# Output.net
KiCad netlist of a schematic drawn in Altium Designer
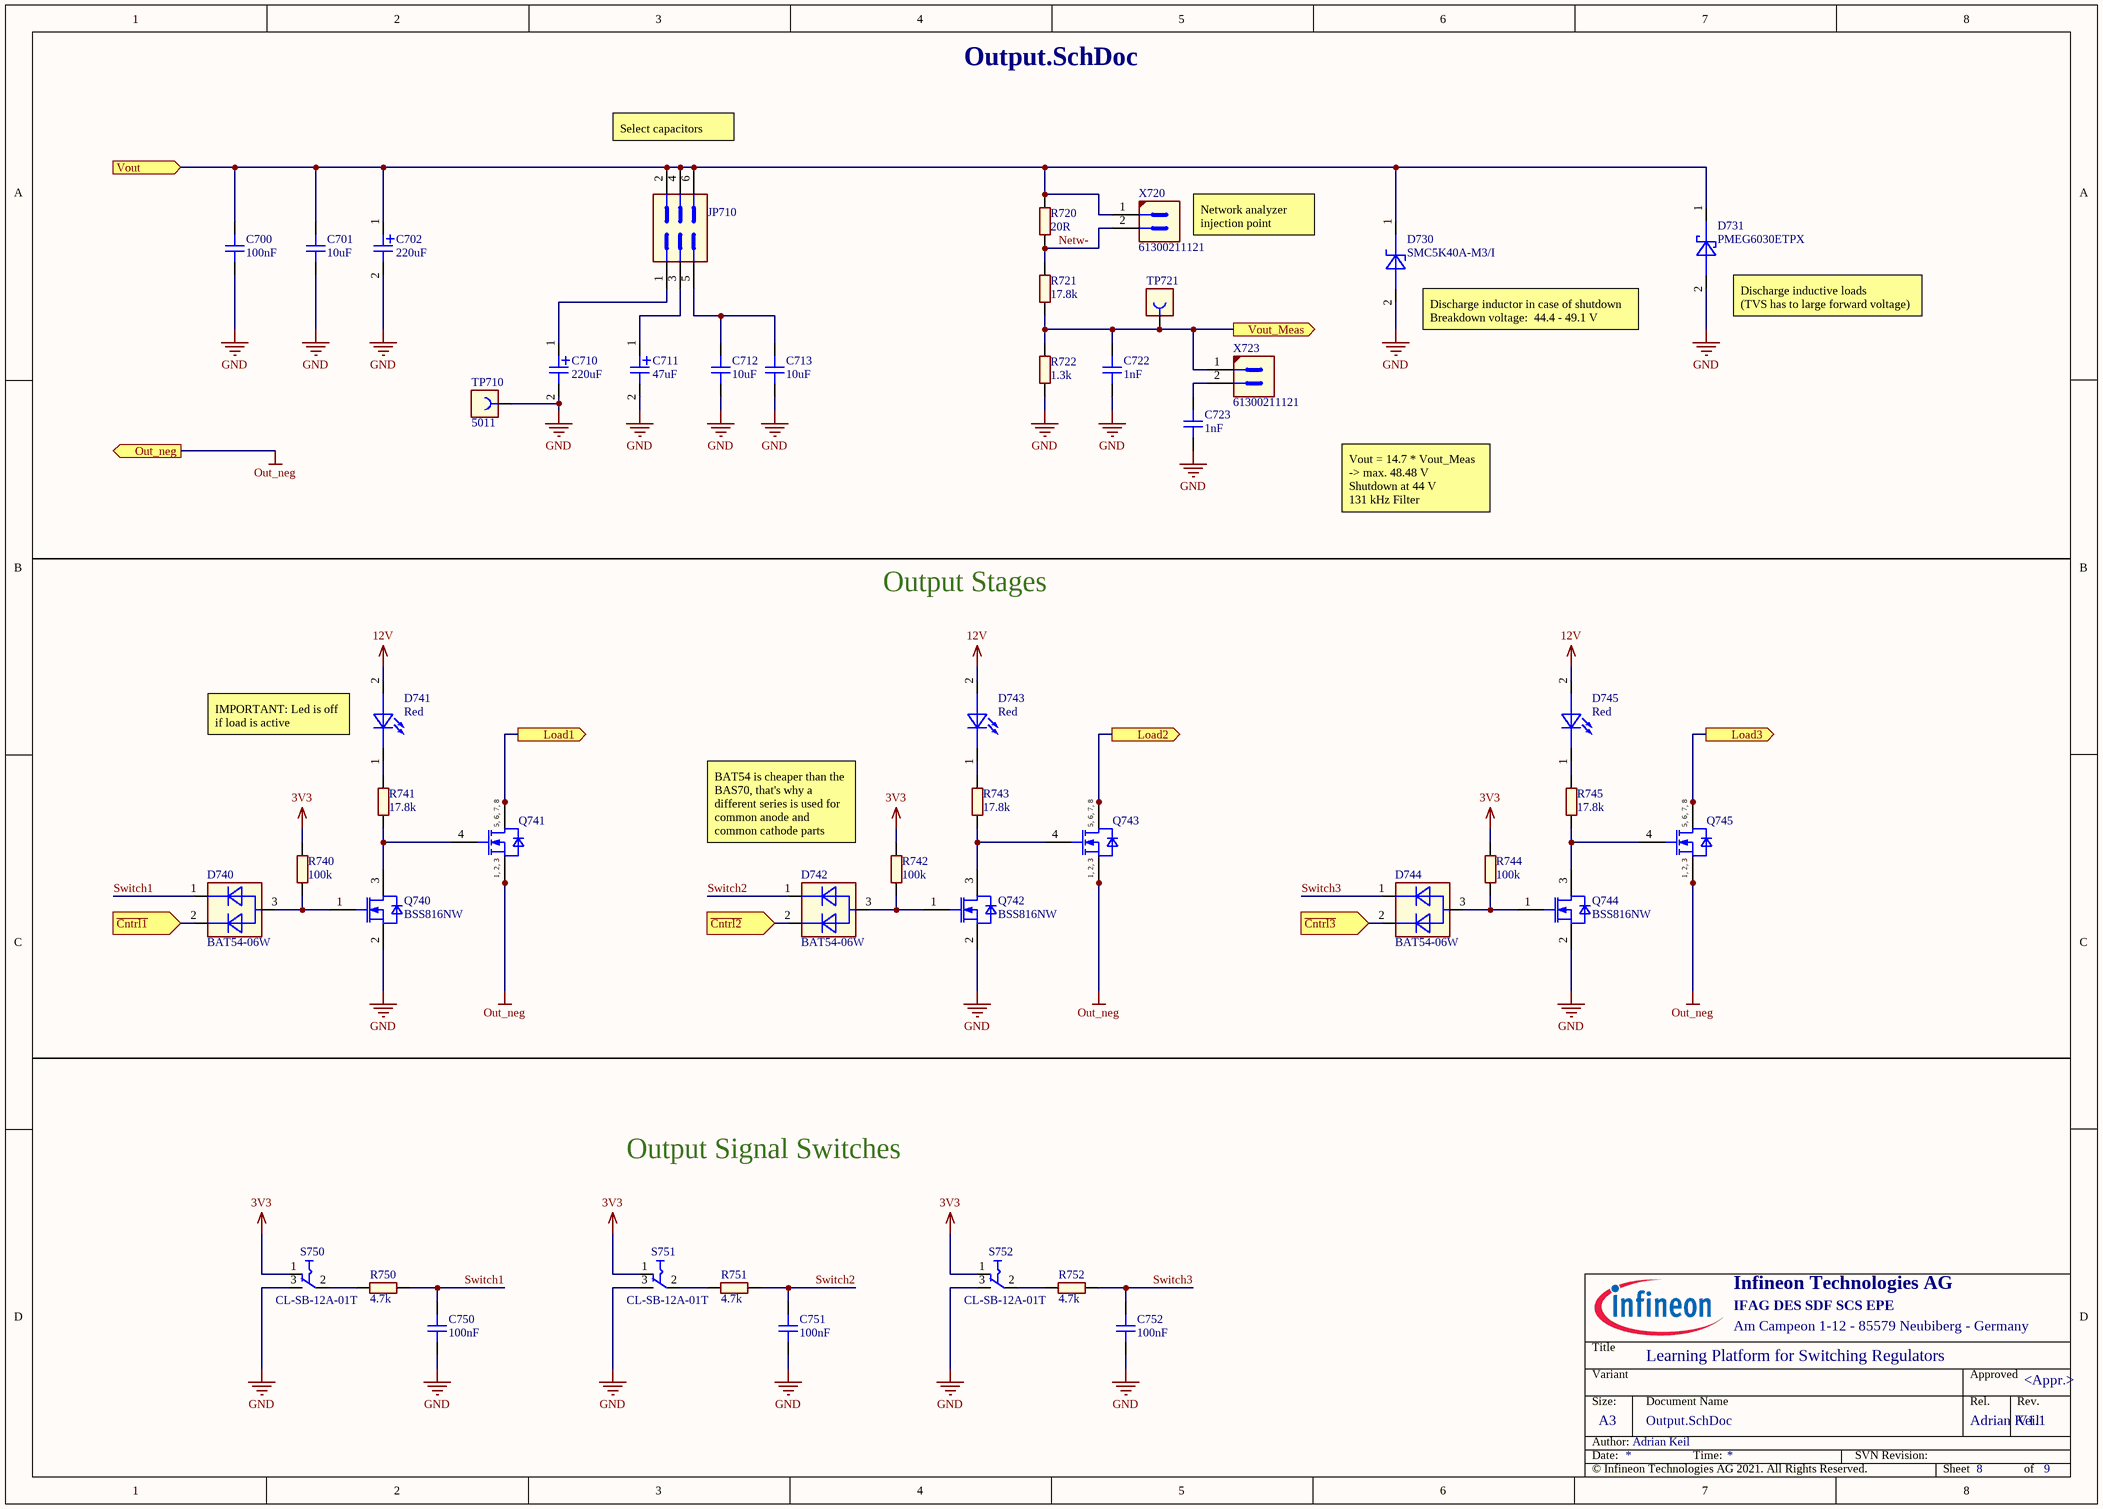
[diagram p0: Output.SchDoc]

(export (version "E")
  (design (tool "Eeschema 10.0.6"))
  (components
    (comp (ref "C700")
      (value "100nF")
      (footprint "CAPC1608X90N-2")
      (description "CAP / CERA / 100nF / 50V / 10% / X7R (EIA) / -55°C to 125°C / 0603 / SMD / -")
      (fields (field (name "MANUFACTURER") "AVX"))
      (libsource (lib "PCBLibraryData") (part "CAP-SGL-STD-02P_00000001"))
    )
    (comp (ref "C701")
      (value "10uF")
      (footprint "CAPC3216X190N-1")
      (description "CAP / CERA / 10uF / 50V / 20% / X5R (EIA) / -55°C to 85°C / 1206 (3216) / SMD / -")
      (fields (field (name "MANUFACTURER") "Taiyo Yuden"))
      (libsource (lib "PCBLibraryData") (part "CAP-SGL-STD-02P_00000001"))
    )
    (comp (ref "C702")
      (value "220uF")
      (footprint "CAPAE1030X1050N-2")
      (fields (field (name "MANUFACTURER") "Wurth Elektronik"))
      (libsource (lib "PCBLibraryData") (part "CAP-SGL-POL-02P_00000002"))
    )
    (comp (ref "C710")
      (value "220uF")
      (footprint "CAPAE1030X1050N-2")
      (fields (field (name "MANUFACTURER") "Wurth Elektronik"))
      (libsource (lib "PCBLibraryData") (part "CAP-SGL-POL-02P_00000002"))
    )
    (comp (ref "C711")
      (value "47uF")
      (footprint "CAPAE660X770N")
      (fields (field (name "MANUFACTURER") "Wurth Elektronik"))
      (libsource (lib "PCBLibraryData") (part "CAP-SGL-POL-02P_00000002"))
    )
    (comp (ref "C712")
      (value "10uF")
      (footprint "CAPC3216X190N-1")
      (description "CAP / CERA / 10uF / 50V / 20% / X5R (EIA) / -55°C to 85°C / 1206 (3216) / SMD / -")
      (fields (field (name "MANUFACTURER") "Taiyo Yuden"))
      (libsource (lib "PCBLibraryData") (part "CAP-SGL-STD-02P_00000001"))
    )
    (comp (ref "C713")
      (value "10uF")
      (footprint "CAPC3216X190N-1")
      (description "CAP / CERA / 10uF / 50V / 20% / X5R (EIA) / -55°C to 85°C / 1206 (3216) / SMD / -")
      (fields (field (name "MANUFACTURER") "Taiyo Yuden"))
      (libsource (lib "PCBLibraryData") (part "CAP-SGL-STD-02P_00000001"))
    )
    (comp (ref "C722")
      (value "1nF")
      (footprint "CAPC1608X87N-1")
      (description "CAP / CERA / 1nF / 50V / 10% / X7R (EIA) / -55°C to 125°C / 0603 (1608) / SMD / -")
      (fields (field (name "MANUFACTURER") "Wurth Elektronik"))
      (libsource (lib "PCBLibraryData") (part "CAP-SGL-STD-02P_00000001"))
    )
    (comp (ref "C723")
      (value "1nF")
      (footprint "CAPC1608X87N-1")
      (description "CAP / CERA / 1nF / 50V / 10% / X7R (EIA) / -55°C to 125°C / 0603 (1608) / SMD / -")
      (fields (field (name "MANUFACTURER") "Wurth Elektronik"))
      (libsource (lib "PCBLibraryData") (part "CAP-SGL-STD-02P_00000001"))
    )
    (comp (ref "C750")
      (value "100nF")
      (footprint "CAPC1608X90N-2")
      (description "CAP / CERA / 100nF / 50V / 10% / X7R (EIA) / -55°C to 125°C / 0603 / SMD / -")
      (fields (field (name "MANUFACTURER") "AVX"))
      (libsource (lib "PCBLibraryData") (part "CAP-SGL-STD-02P_00000001"))
    )
    (comp (ref "C751")
      (value "100nF")
      (footprint "CAPC1608X90N-2")
      (description "CAP / CERA / 100nF / 50V / 10% / X7R (EIA) / -55°C to 125°C / 0603 / SMD / -")
      (fields (field (name "MANUFACTURER") "AVX"))
      (libsource (lib "PCBLibraryData") (part "CAP-SGL-STD-02P_00000001"))
    )
    (comp (ref "C752")
      (value "100nF")
      (footprint "CAPC1608X90N-2")
      (description "CAP / CERA / 100nF / 50V / 10% / X7R (EIA) / -55°C to 125°C / 0603 / SMD / -")
      (fields (field (name "MANUFACTURER") "AVX"))
      (libsource (lib "PCBLibraryData") (part "CAP-SGL-STD-02P_00000001"))
    )
    (comp (ref "D730")
      (value "SMC5K40A-M3/I")
      (footprint "DIOM7959X262N")
      (description "Surface Mount Transient Voltage Suppressors, Unidirectional, Very Fast Response Time")
      (fields (field (name "MANUFACTURER") "Vishay"))
      (libsource (lib "PCBLibraryData") (part "d_tvs_a"))
    )
    (comp (ref "D731")
      (value "PMEG6030ETPX")
      (footprint "SODFL4725X110N")
      (description "DIODE SCHOTTKY 60V 3A SOD128")
      (fields (field (name "MANUFACTURER") "Nexperia"))
      (libsource (lib "PCBLibraryData") (part "d_schottky_a"))
    )
    (comp (ref "D740")
      (value "BAT54-06W")
      (footprint "SOT65P210X100-3N-1-V")
      (description "Silicon Schottky Diodes")
      (fields (field (name "MANUFACTURER") "Infineon Technologies"))
      (libsource (lib "PCBLibraryData") (part "d_dual_c1c2a3_3p"))
    )
    (comp (ref "D741")
      (value "Red")
      (footprint "LEDSC160X80X80-2N-1")
      (description "WL-SMCW SMT Mono-color Chip LED Waterclear, Red,630nm")
      (fields (field (name "MANUFACTURER") "Wurth Elektronik"))
      (libsource (lib "PCBLibraryData") (part "d_led_a"))
    )
    (comp (ref "D742")
      (value "BAT54-06W")
      (footprint "SOT65P210X100-3N-1-V")
      (description "Silicon Schottky Diodes")
      (fields (field (name "MANUFACTURER") "Infineon Technologies"))
      (libsource (lib "PCBLibraryData") (part "d_dual_c1c2a3_3p"))
    )
    (comp (ref "D743")
      (value "Red")
      (footprint "LEDSC160X80X80-2N-1")
      (description "WL-SMCW SMT Mono-color Chip LED Waterclear, Red,630nm")
      (fields (field (name "MANUFACTURER") "Wurth Elektronik"))
      (libsource (lib "PCBLibraryData") (part "d_led_a"))
    )
    (comp (ref "D744")
      (value "BAT54-06W")
      (footprint "SOT65P210X100-3N-1-V")
      (description "Silicon Schottky Diodes")
      (fields (field (name "MANUFACTURER") "Infineon Technologies"))
      (libsource (lib "PCBLibraryData") (part "d_dual_c1c2a3_3p"))
    )
    (comp (ref "D745")
      (value "Red")
      (footprint "LEDSC160X80X80-2N-1")
      (description "WL-SMCW SMT Mono-color Chip LED Waterclear, Red,630nm")
      (fields (field (name "MANUFACTURER") "Wurth Elektronik"))
      (libsource (lib "PCBLibraryData") (part "d_led_a"))
    )
    (comp (ref "JP710")
      (value "Header 3X2A")
      (footprint "CON-M-THT-61300621121")
      (description "WR-PHD Dual Pin Header, 2.54mm Pitch, Double row, 6 Pins")
      (fields (field (name "MANUFACTURER") "Wurth Elektronik"))
      (libsource (lib "PCBLibraryData") (part "Header 3X2A"))
    )
    (comp (ref "Q740")
      (value "BSS816NW")
      (footprint "SOT65P210X100-3N-1-V")
      (description "OptiMOS 2 Small-Signal-Transistor")
      (fields (field (name "MANUFACTURER") "Infineon Technologies"))
      (libsource (lib "PCBLibraryData") (part "igfet_n_ch_dep_dio_1g2s3d_3p"))
    )
    (comp (ref "Q741")
      (value "igfet_n_ch_enh_dio_1s2s3s4g5d6d7d8d_8p")
      (footprint "INF-PG-TSDSON-8-FL")
      (description "OptiMOS Power - MOSFET, 60 V")
      (fields
        (field (name "LEGACY PARTNUMBER") "IFX01400359")
        (field (name "MANUFACTURER") "Infineon Technologies")
      )
      (libsource (lib "PCBLibraryData") (part "igfet_n_ch_enh_dio_1s2s3s4g5d6d7d8d_8p"))
    )
    (comp (ref "Q742")
      (value "BSS816NW")
      (footprint "SOT65P210X100-3N-1-V")
      (description "OptiMOS 2 Small-Signal-Transistor")
      (fields (field (name "MANUFACTURER") "Infineon Technologies"))
      (libsource (lib "PCBLibraryData") (part "igfet_n_ch_dep_dio_1g2s3d_3p"))
    )
    (comp (ref "Q743")
      (value "igfet_n_ch_enh_dio_1s2s3s4g5d6d7d8d_8p")
      (footprint "INF-PG-TSDSON-8-FL")
      (description "OptiMOS Power - MOSFET, 60 V")
      (fields
        (field (name "LEGACY PARTNUMBER") "IFX01400359")
        (field (name "MANUFACTURER") "Infineon Technologies")
      )
      (libsource (lib "PCBLibraryData") (part "igfet_n_ch_enh_dio_1s2s3s4g5d6d7d8d_8p"))
    )
    (comp (ref "Q744")
      (value "BSS816NW")
      (footprint "SOT65P210X100-3N-1-V")
      (description "OptiMOS 2 Small-Signal-Transistor")
      (fields (field (name "MANUFACTURER") "Infineon Technologies"))
      (libsource (lib "PCBLibraryData") (part "igfet_n_ch_dep_dio_1g2s3d_3p"))
    )
    (comp (ref "Q745")
      (value "igfet_n_ch_enh_dio_1s2s3s4g5d6d7d8d_8p")
      (footprint "INF-PG-TSDSON-8-FL")
      (description "OptiMOS Power - MOSFET, 60 V")
      (fields
        (field (name "LEGACY PARTNUMBER") "IFX01400359")
        (field (name "MANUFACTURER") "Infineon Technologies")
      )
      (libsource (lib "PCBLibraryData") (part "igfet_n_ch_enh_dio_1s2s3s4g5d6d7d8d_8p"))
    )
    (comp (ref "R720")
      (value "20R")
      (footprint "RESC1609X50N")
      (description "RES / STD / 20R / 100mW / 1% / 100ppm/K / -55°C to 155°C / 0603 / SMD / -")
      (fields (field (name "LEGACY PARTNUMBER") "RES01800947") (field (name "MANUFACTURER") "Vishay"))
      (libsource (lib "PCBLibraryData") (part "RES-SGL-STD-02P_00000006"))
    )
    (comp (ref "R721")
      (value "17.8k")
      (footprint "RESC1609X50N")
      (description "RES / STD / 17.8k / 100mW / 1% / 100ppm/K / -55°C to 155°C / 0603 / SMD / -")
      (fields (field (name "LEGACY PARTNUMBER") "RES01801283") (field (name "MANUFACTURER") "Vishay"))
      (libsource (lib "") (part "RES-SGL-STD-02P_00000006_2"))
    )
    (comp (ref "R722")
      (value "1.3k")
      (footprint "RESC1609X50N")
      (description "RES / STD / 1.3k / 100mW / 1% / 100ppm/K / -55°C to 155°C / 0603 / SMD / -")
      (fields (field (name "LEGACY PARTNUMBER") "RES01801155") (field (name "MANUFACTURER") "Vishay"))
      (libsource (lib "PCBLibraryData") (part "RES-SGL-STD-02P_00000006"))
    )
    (comp (ref "R740")
      (value "100k")
      (footprint "RESC1609X50N")
      (description "RES / STD / 100k / 100mW / 1% / 100ppm/K / -55°C to 155°C / 0603 / SMD / -")
      (fields (field (name "LEGACY PARTNUMBER") "RES01801371") (field (name "MANUFACTURER") "Vishay"))
      (libsource (lib "PCBLibraryData") (part "RES-SGL-STD-02P_00000006"))
    )
    (comp (ref "R741")
      (value "17.8k")
      (footprint "RESC1609X50N")
      (description "RES / STD / 17.8k / 100mW / 1% / 100ppm/K / -55°C to 155°C / 0603 / SMD / -")
      (fields (field (name "LEGACY PARTNUMBER") "RES01801283") (field (name "MANUFACTURER") "Vishay"))
      (libsource (lib "PCBLibraryData") (part "RES-SGL-STD-02P_00000006"))
    )
    (comp (ref "R742")
      (value "100k")
      (footprint "RESC1609X50N")
      (description "RES / STD / 100k / 100mW / 1% / 100ppm/K / -55°C to 155°C / 0603 / SMD / -")
      (fields (field (name "LEGACY PARTNUMBER") "RES01801371") (field (name "MANUFACTURER") "Vishay"))
      (libsource (lib "PCBLibraryData") (part "RES-SGL-STD-02P_00000006"))
    )
    (comp (ref "R743")
      (value "17.8k")
      (footprint "RESC1609X50N")
      (description "RES / STD / 17.8k / 100mW / 1% / 100ppm/K / -55°C to 155°C / 0603 / SMD / -")
      (fields (field (name "LEGACY PARTNUMBER") "RES01801283") (field (name "MANUFACTURER") "Vishay"))
      (libsource (lib "PCBLibraryData") (part "RES-SGL-STD-02P_00000006"))
    )
    (comp (ref "R744")
      (value "100k")
      (footprint "RESC1609X50N")
      (description "RES / STD / 100k / 100mW / 1% / 100ppm/K / -55°C to 155°C / 0603 / SMD / -")
      (fields (field (name "LEGACY PARTNUMBER") "RES01801371") (field (name "MANUFACTURER") "Vishay"))
      (libsource (lib "PCBLibraryData") (part "RES-SGL-STD-02P_00000006"))
    )
    (comp (ref "R745")
      (value "17.8k")
      (footprint "RESC1609X50N")
      (description "RES / STD / 17.8k / 100mW / 1% / 100ppm/K / -55°C to 155°C / 0603 / SMD / -")
      (fields (field (name "LEGACY PARTNUMBER") "RES01801283") (field (name "MANUFACTURER") "Vishay"))
      (libsource (lib "PCBLibraryData") (part "RES-SGL-STD-02P_00000006"))
    )
    (comp (ref "R750")
      (value "4.7k")
      (footprint "RESC1609X50N")
      (description "RES / STD / 4.7k / 100mW / 1% / 100ppm/K / -55°C to 155°C / 0603 / SMD / -")
      (fields (field (name "LEGACY PARTNUMBER") "RES01801219") (field (name "MANUFACTURER") "Vishay"))
      (libsource (lib "") (part "RES-SGL-STD-02P_00000006_1"))
    )
    (comp (ref "R751")
      (value "4.7k")
      (footprint "RESC1609X50N")
      (description "RES / STD / 4.7k / 100mW / 1% / 100ppm/K / -55°C to 155°C / 0603 / SMD / -")
      (fields (field (name "LEGACY PARTNUMBER") "RES01801219") (field (name "MANUFACTURER") "Vishay"))
      (libsource (lib "") (part "RES-SGL-STD-02P_00000006_1"))
    )
    (comp (ref "R752")
      (value "4.7k")
      (footprint "RESC1609X50N")
      (description "RES / STD / 4.7k / 100mW / 1% / 100ppm/K / -55°C to 155°C / 0603 / SMD / -")
      (fields (field (name "LEGACY PARTNUMBER") "RES01801219") (field (name "MANUFACTURER") "Vishay"))
      (libsource (lib "") (part "RES-SGL-STD-02P_00000006_1"))
    )
    (comp (ref "S750")
      (value "CL-SB-12A-01T")
      (footprint "SW-SMD-CL-SB-12A-01T")
      (description "Slid Switch, 12V, 200mA")
      (fields (field (name "MANUFACTURER") "NIDEC COPAL ELECTRONICS, Inc."))
      (libsource (lib "PCBLibraryData") (part "sw_co213_3p"))
    )
    (comp (ref "S751")
      (value "CL-SB-12A-01T")
      (footprint "SW-SMD-CL-SB-12A-01T")
      (description "Slid Switch, 12V, 200mA")
      (fields (field (name "MANUFACTURER") "NIDEC COPAL ELECTRONICS, Inc."))
      (libsource (lib "PCBLibraryData") (part "sw_co213_3p"))
    )
    (comp (ref "S752")
      (value "CL-SB-12A-01T")
      (footprint "SW-SMD-CL-SB-12A-01T")
      (description "Slid Switch, 12V, 200mA")
      (fields (field (name "MANUFACTURER") "NIDEC COPAL ELECTRONICS, Inc."))
      (libsource (lib "PCBLibraryData") (part "sw_co213_3p"))
    )
    (comp (ref "TP710")
      (value "5011")
      (footprint "CON-THT-TP-5011")
      (description "PC Test Point-Multipurpose THT, Black")
      (fields
        (field (name "LEGACY PARTNUMBER") "CON01500530")
        (field (name "MANUFACTURER") "Keystone Electronics Corp.")
      )
      (libsource (lib "PCBLibraryData") (part "connector_1_f"))
    )
    (comp (ref "TP721")
      (value "S1751-46R")
      (footprint "CON-SMD-TT-S1751-46")
      (description "Test Terminal, Surface Mount (Tape and Reeled Components)")
      (fields (field (name "LEGACY PARTNUMBER") "CON01501015") (field (name "MANUFACTURER") "Harwin"))
      (libsource (lib "") (part "connector_1_f_1"))
    )
    (comp (ref "X720")
      (value "61300211121")
      (footprint "CON-M-THT-61300211121")
      (description "Header, 2.54mm Pitch, 2 pin, Vertical, Single Row")
      (fields
        (field (name "LEGACY PARTNUMBER") "CON01500943")
        (field (name "MANUFACTURER") "Wurth Elektronik")
      )
      (libsource (lib "PCBLibraryData") (part "Header 2"))
    )
    (comp (ref "X723")
      (value "61300211121")
      (footprint "CON-M-THT-61300211121")
      (description "Header, 2.54mm Pitch, 2 pin, Vertical, Single Row")
      (fields
        (field (name "LEGACY PARTNUMBER") "CON01500943")
        (field (name "MANUFACTURER") "Wurth Elektronik")
      )
      (libsource (lib "PCBLibraryData") (part "Header 2"))
    )
  )
  (nets
    (net (code "1") (name "/Cntrl1") (class "Default")
      (node (ref "D740") (pin "2") (pinfunction "CATHODE2_2") (pintype "passive"))
    )
    (net (code "2") (name "/Cntrl2") (class "Default")
      (node (ref "D742") (pin "2") (pinfunction "CATHODE2_2") (pintype "passive"))
    )
    (net (code "3") (name "/Cntrl3") (class "Default")
      (node (ref "D744") (pin "2") (pinfunction "CATHODE2_2") (pintype "passive"))
    )
    (net (code "4") (name "/Load1") (class "Default")
      (node (ref "Q741") (pin "5") (pinfunction "DRAIN_5") (pintype "passive"))
      (node (ref "Q741") (pin "6") (pinfunction "DRAIN_6") (pintype "passive"))
      (node (ref "Q741") (pin "7") (pinfunction "DRAIN_7") (pintype "passive"))
      (node (ref "Q741") (pin "8") (pinfunction "DRAIN_8") (pintype "passive"))
    )
    (net (code "5") (name "/Load2") (class "Default")
      (node (ref "Q743") (pin "5") (pinfunction "DRAIN_5") (pintype "passive"))
      (node (ref "Q743") (pin "6") (pinfunction "DRAIN_6") (pintype "passive"))
      (node (ref "Q743") (pin "7") (pinfunction "DRAIN_7") (pintype "passive"))
      (node (ref "Q743") (pin "8") (pinfunction "DRAIN_8") (pintype "passive"))
    )
    (net (code "6") (name "/Load3") (class "Default")
      (node (ref "Q745") (pin "5") (pinfunction "DRAIN_5") (pintype "passive"))
      (node (ref "Q745") (pin "6") (pinfunction "DRAIN_6") (pintype "passive"))
      (node (ref "Q745") (pin "7") (pinfunction "DRAIN_7") (pintype "passive"))
      (node (ref "Q745") (pin "8") (pinfunction "DRAIN_8") (pintype "passive"))
    )
    (net (code "7") (name "/Netw-") (class "Default")
      (node (ref "R720") (pin "1") (pinfunction "1_1") (pintype "passive"))
      (node (ref "R721") (pin "1") (pinfunction "1_1") (pintype "passive"))
      (node (ref "X720") (pin "2") (pinfunction "2_2") (pintype "passive"))
    )
    (net (code "8") (name "/Switch1") (class "Default")
      (node (ref "C750") (pin "2") (pinfunction "2_2") (pintype "passive"))
      (node (ref "D740") (pin "1") (pinfunction "CATHODE1_1") (pintype "passive"))
      (node (ref "R750") (pin "2") (pinfunction "2_2") (pintype "passive"))
    )
    (net (code "9") (name "/Switch2") (class "Default")
      (node (ref "C751") (pin "2") (pinfunction "2_2") (pintype "passive"))
      (node (ref "D742") (pin "1") (pinfunction "CATHODE1_1") (pintype "passive"))
      (node (ref "R751") (pin "2") (pinfunction "2_2") (pintype "passive"))
    )
    (net (code "10") (name "/Switch3") (class "Default")
      (node (ref "C752") (pin "2") (pinfunction "2_2") (pintype "passive"))
      (node (ref "D744") (pin "1") (pinfunction "CATHODE1_1") (pintype "passive"))
      (node (ref "R752") (pin "2") (pinfunction "2_2") (pintype "passive"))
    )
    (net (code "11") (name "/Vout") (class "Default")
      (node (ref "C700") (pin "2") (pinfunction "2_2") (pintype "passive"))
      (node (ref "C701") (pin "2") (pinfunction "2_2") (pintype "passive"))
      (node (ref "C702") (pin "1") (pinfunction "1_1") (pintype "passive"))
      (node (ref "D730") (pin "1") (pinfunction "CATHODE_1") (pintype "passive"))
      (node (ref "D731") (pin "1") (pinfunction "Cathode_1") (pintype "passive"))
      (node (ref "JP710") (pin "2") (pinfunction "2_2") (pintype "passive"))
      (node (ref "JP710") (pin "4") (pinfunction "4_4") (pintype "passive"))
      (node (ref "JP710") (pin "6") (pinfunction "6_6") (pintype "passive"))
      (node (ref "R720") (pin "2") (pinfunction "2_2") (pintype "passive"))
      (node (ref "X720") (pin "1") (pinfunction "1_1") (pintype "passive"))
    )
    (net (code "12") (name "/Vout_Meas") (class "Default")
      (node (ref "C722") (pin "2") (pinfunction "2_2") (pintype "passive"))
      (node (ref "R721") (pin "2") (pinfunction "2_2") (pintype "passive"))
      (node (ref "R722") (pin "2") (pinfunction "2_2") (pintype "passive"))
      (node (ref "TP721") (pin "1") (pinfunction "1_1") (pintype "passive"))
      (node (ref "X723") (pin "1") (pinfunction "1_1") (pintype "passive"))
    )
    (net (code "13") (name "3V3") (class "Default")
      (node (ref "R740") (pin "2") (pinfunction "2_2") (pintype "passive"))
      (node (ref "R742") (pin "2") (pinfunction "2_2") (pintype "passive"))
      (node (ref "R744") (pin "2") (pinfunction "2_2") (pintype "passive"))
      (node (ref "S750") (pin "1") (pinfunction "1_1") (pintype "passive"))
      (node (ref "S751") (pin "1") (pinfunction "1_1") (pintype "passive"))
      (node (ref "S752") (pin "1") (pinfunction "1_1") (pintype "passive"))
    )
    (net (code "14") (name "12V") (class "Default")
      (node (ref "D741") (pin "2") (pinfunction "Anode_2") (pintype "passive"))
      (node (ref "D743") (pin "2") (pinfunction "Anode_2") (pintype "passive"))
      (node (ref "D745") (pin "2") (pinfunction "Anode_2") (pintype "passive"))
    )
    (net (code "15") (name "GND") (class "Default")
      (node (ref "C700") (pin "1") (pinfunction "1_1") (pintype "passive"))
      (node (ref "C701") (pin "1") (pinfunction "1_1") (pintype "passive"))
      (node (ref "C702") (pin "2") (pinfunction "2_2") (pintype "passive"))
      (node (ref "C710") (pin "2") (pinfunction "2_2") (pintype "passive"))
      (node (ref "C711") (pin "2") (pinfunction "2_2") (pintype "passive"))
      (node (ref "C712") (pin "1") (pinfunction "1_1") (pintype "passive"))
      (node (ref "C713") (pin "1") (pinfunction "1_1") (pintype "passive"))
      (node (ref "C722") (pin "1") (pinfunction "1_1") (pintype "passive"))
      (node (ref "C723") (pin "1") (pinfunction "1_1") (pintype "passive"))
      (node (ref "C750") (pin "1") (pinfunction "1_1") (pintype "passive"))
      (node (ref "C751") (pin "1") (pinfunction "1_1") (pintype "passive"))
      (node (ref "C752") (pin "1") (pinfunction "1_1") (pintype "passive"))
      (node (ref "D730") (pin "2") (pinfunction "ANODE_2") (pintype "passive"))
      (node (ref "D731") (pin "2") (pinfunction "Anode_2") (pintype "passive"))
      (node (ref "Q740") (pin "2") (pinfunction "SOURCE_2") (pintype "passive"))
      (node (ref "Q742") (pin "2") (pinfunction "SOURCE_2") (pintype "passive"))
      (node (ref "Q744") (pin "2") (pinfunction "SOURCE_2") (pintype "passive"))
      (node (ref "R722") (pin "1") (pinfunction "1_1") (pintype "passive"))
      (node (ref "S750") (pin "3") (pinfunction "3_3") (pintype "passive"))
      (node (ref "S751") (pin "3") (pinfunction "3_3") (pintype "passive"))
      (node (ref "S752") (pin "3") (pinfunction "3_3") (pintype "passive"))
      (node (ref "TP710") (pin "1") (pinfunction "1_1") (pintype "passive"))
    )
    (net (code "16") (name "Net-(C710-Pad1)") (class "Default")
      (node (ref "C710") (pin "1") (pinfunction "1_1") (pintype "passive"))
      (node (ref "JP710") (pin "1") (pinfunction "1_1") (pintype "passive"))
    )
    (net (code "17") (name "Net-(C711-Pad1)") (class "Default")
      (node (ref "C711") (pin "1") (pinfunction "1_1") (pintype "passive"))
      (node (ref "JP710") (pin "3") (pinfunction "3_3") (pintype "passive"))
    )
    (net (code "18") (name "Net-(C712-Pad2)") (class "Default")
      (node (ref "C712") (pin "2") (pinfunction "2_2") (pintype "passive"))
      (node (ref "C713") (pin "2") (pinfunction "2_2") (pintype "passive"))
      (node (ref "JP710") (pin "5") (pinfunction "5_5") (pintype "passive"))
    )
    (net (code "19") (name "Net-(C723-Pad2)") (class "Default")
      (node (ref "C723") (pin "2") (pinfunction "2_2") (pintype "passive"))
      (node (ref "X723") (pin "2") (pinfunction "2_2") (pintype "passive"))
    )
    (net (code "20") (name "Net-(D740-ANODE)") (class "Default")
      (node (ref "D740") (pin "3") (pinfunction "ANODE_3") (pintype "passive"))
      (node (ref "Q740") (pin "1") (pinfunction "GATE_1") (pintype "passive"))
      (node (ref "R740") (pin "1") (pinfunction "1_1") (pintype "passive"))
    )
    (net (code "21") (name "Net-(D741-Cathode)") (class "Default")
      (node (ref "D741") (pin "1") (pinfunction "Cathode_1") (pintype "passive"))
      (node (ref "R741") (pin "2") (pinfunction "2_2") (pintype "passive"))
    )
    (net (code "22") (name "Net-(D742-ANODE)") (class "Default")
      (node (ref "D742") (pin "3") (pinfunction "ANODE_3") (pintype "passive"))
      (node (ref "Q742") (pin "1") (pinfunction "GATE_1") (pintype "passive"))
      (node (ref "R742") (pin "1") (pinfunction "1_1") (pintype "passive"))
    )
    (net (code "23") (name "Net-(D743-Cathode)") (class "Default")
      (node (ref "D743") (pin "1") (pinfunction "Cathode_1") (pintype "passive"))
      (node (ref "R743") (pin "2") (pinfunction "2_2") (pintype "passive"))
    )
    (net (code "24") (name "Net-(D744-ANODE)") (class "Default")
      (node (ref "D744") (pin "3") (pinfunction "ANODE_3") (pintype "passive"))
      (node (ref "Q744") (pin "1") (pinfunction "GATE_1") (pintype "passive"))
      (node (ref "R744") (pin "1") (pinfunction "1_1") (pintype "passive"))
    )
    (net (code "25") (name "Net-(D745-Cathode)") (class "Default")
      (node (ref "D745") (pin "1") (pinfunction "Cathode_1") (pintype "passive"))
      (node (ref "R745") (pin "2") (pinfunction "2_2") (pintype "passive"))
    )
    (net (code "26") (name "Net-(Q740-DRAIN)") (class "Default")
      (node (ref "Q740") (pin "3") (pinfunction "DRAIN_3") (pintype "passive"))
      (node (ref "Q741") (pin "4") (pinfunction "GATE_4") (pintype "passive"))
      (node (ref "R741") (pin "1") (pinfunction "1_1") (pintype "passive"))
    )
    (net (code "27") (name "Net-(Q742-DRAIN)") (class "Default")
      (node (ref "Q742") (pin "3") (pinfunction "DRAIN_3") (pintype "passive"))
      (node (ref "Q743") (pin "4") (pinfunction "GATE_4") (pintype "passive"))
      (node (ref "R743") (pin "1") (pinfunction "1_1") (pintype "passive"))
    )
    (net (code "28") (name "Net-(Q744-DRAIN)") (class "Default")
      (node (ref "Q744") (pin "3") (pinfunction "DRAIN_3") (pintype "passive"))
      (node (ref "Q745") (pin "4") (pinfunction "GATE_4") (pintype "passive"))
      (node (ref "R745") (pin "1") (pinfunction "1_1") (pintype "passive"))
    )
    (net (code "29") (name "Net-(R750-Pad1)") (class "Default")
      (node (ref "R750") (pin "1") (pinfunction "1_1") (pintype "passive"))
      (node (ref "S750") (pin "2") (pinfunction "2_2") (pintype "passive"))
    )
    (net (code "30") (name "Net-(R751-Pad1)") (class "Default")
      (node (ref "R751") (pin "1") (pinfunction "1_1") (pintype "passive"))
      (node (ref "S751") (pin "2") (pinfunction "2_2") (pintype "passive"))
    )
    (net (code "31") (name "Net-(R752-Pad1)") (class "Default")
      (node (ref "R752") (pin "1") (pinfunction "1_1") (pintype "passive"))
      (node (ref "S752") (pin "2") (pinfunction "2_2") (pintype "passive"))
    )
    (net (code "32") (name "Out_neg") (class "Default")
      (node (ref "Q741") (pin "1") (pinfunction "SOURCE_1") (pintype "passive"))
      (node (ref "Q741") (pin "2") (pinfunction "SOURCE_2") (pintype "passive"))
      (node (ref "Q741") (pin "3") (pinfunction "SOURCE_3") (pintype "passive"))
      (node (ref "Q743") (pin "1") (pinfunction "SOURCE_1") (pintype "passive"))
      (node (ref "Q743") (pin "2") (pinfunction "SOURCE_2") (pintype "passive"))
      (node (ref "Q743") (pin "3") (pinfunction "SOURCE_3") (pintype "passive"))
      (node (ref "Q745") (pin "1") (pinfunction "SOURCE_1") (pintype "passive"))
      (node (ref "Q745") (pin "2") (pinfunction "SOURCE_2") (pintype "passive"))
      (node (ref "Q745") (pin "3") (pinfunction "SOURCE_3") (pintype "passive"))
    )
  )
)
